# VoltageDivider.net
KiCad netlist of a schematic drawn in Altium Designer
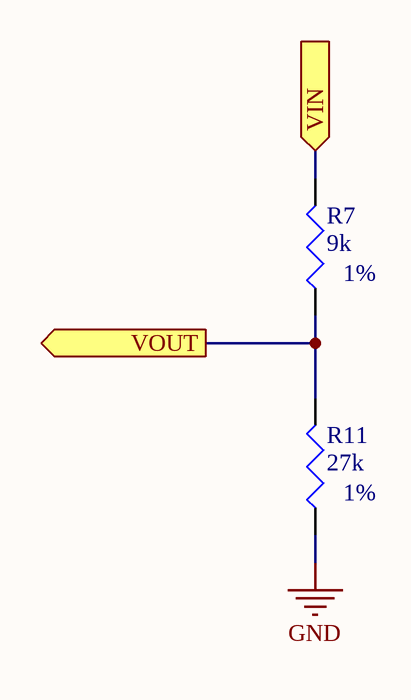
[diagram p0: VoltageDivider.SchDoc]

(export (version "E")
  (design (tool "Eeschema 10.0.6"))
  (components
    (comp (ref "R7")
      (value "1%")
      (footprint "J1-0603")
      (description "Resistor")
      (fields (field (name "ALTIUM_VALUE") "9k") (field (name "PUBLISHER") "Altium Limited"))
      (libsource (lib "Miscellaneous Devices") (part "Res3"))
    )
    (comp (ref "R11")
      (value "1%")
      (footprint "J1-0603")
      (description "Resistor")
      (fields (field (name "ALTIUM_VALUE") "27k") (field (name "PUBLISHER") "Altium Limited"))
      (libsource (lib "Miscellaneous Devices") (part "Res3"))
    )
  )
  (nets
    (net (code "1") (name "/VIN") (class "Default")
      (node (ref "R7") (pin "2") (pinfunction "2_2") (pintype "passive"))
    )
    (net (code "2") (name "/VOUT") (class "Default")
      (node (ref "R11") (pin "2") (pinfunction "2_2") (pintype "passive"))
      (node (ref "R7") (pin "1") (pinfunction "1_1") (pintype "passive"))
    )
    (net (code "3") (name "GND") (class "Default")
      (node (ref "R11") (pin "1") (pinfunction "1_1") (pintype "passive"))
    )
  )
)
